# kumand.net
KiCad netlist of a schematic drawn in EAGLE
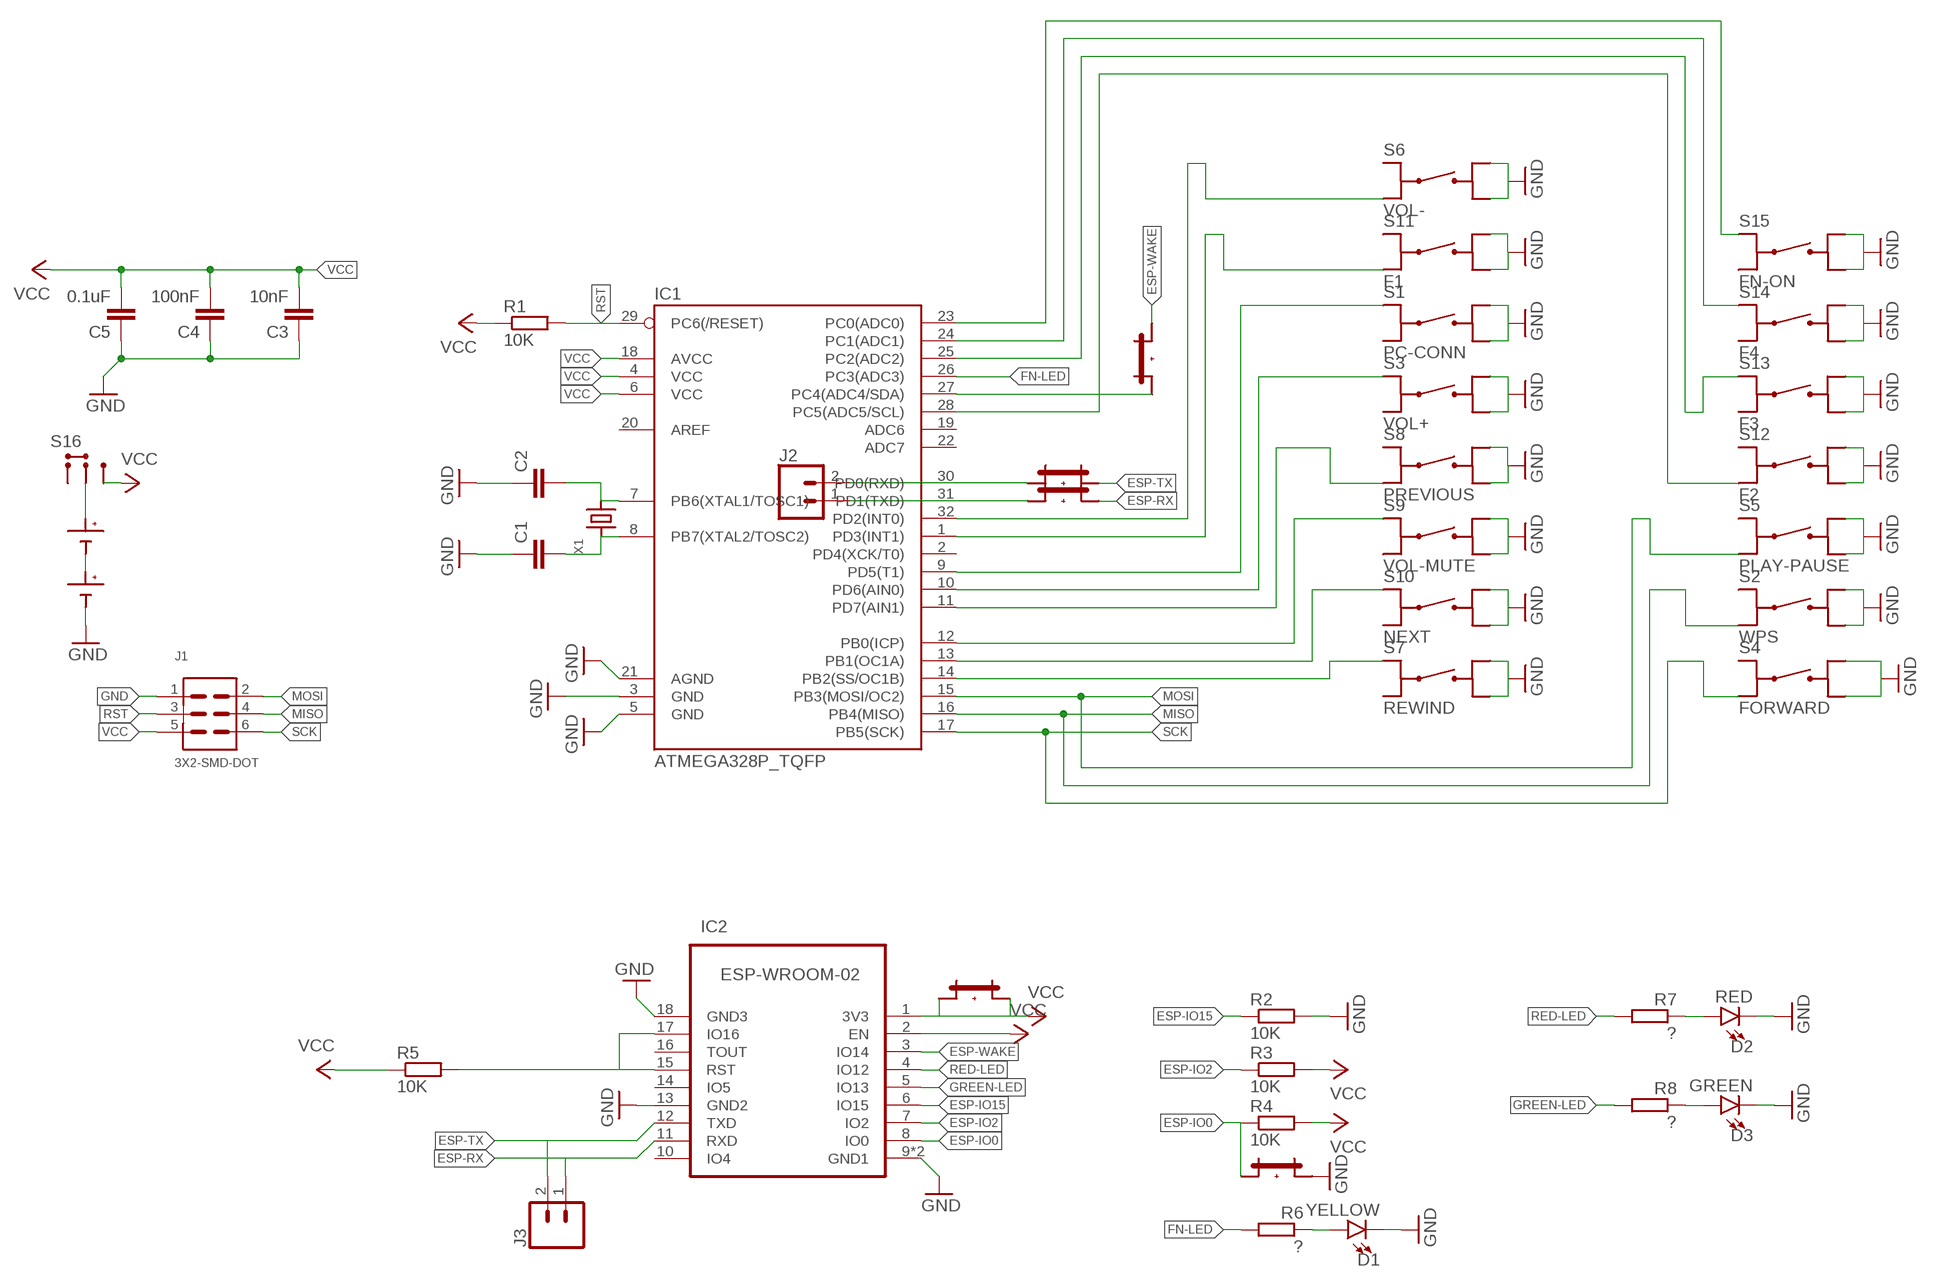
[diagram p0: schematic, sheet 1]

(export (version "E")
  (design (tool "Eeschema 10.0.6"))
  (components
    (comp (ref "C1")
      (value "C-EUC1206")
      (footprint "eagle-import:C1206")
      (libsource (lib "eagle-import") (part "C-EUC1206"))
    )
    (comp (ref "C2")
      (value "C-EUC1206")
      (footprint "eagle-import:C1206")
      (libsource (lib "eagle-import") (part "C-EUC1206"))
    )
    (comp (ref "C3")
      (value "10nF")
      (footprint "eagle-import:C1206")
      (libsource (lib "eagle-import") (part "C-EUC1206"))
    )
    (comp (ref "C4")
      (value "100nF")
      (footprint "eagle-import:C1206")
      (libsource (lib "eagle-import") (part "C-EUC1206"))
    )
    (comp (ref "C5")
      (value "0.1uF")
      (footprint "eagle-import:C1206")
      (libsource (lib "eagle-import") (part "C-EUC1206"))
    )
    (comp (ref "D1")
      (value "YELLOW")
      (footprint "eagle-import:LED-1206")
      (libsource (lib "eagle-import") (part "LED1206"))
    )
    (comp (ref "D2")
      (value "RED")
      (footprint "eagle-import:LED-1206")
      (libsource (lib "eagle-import") (part "LED1206"))
    )
    (comp (ref "D3")
      (value "GREEN")
      (footprint "eagle-import:LED-1206")
      (libsource (lib "eagle-import") (part "LED1206"))
    )
    (comp (ref "IC1")
      (value "ATMEGA328P_TQFP")
      (footprint "eagle-import:TQFP32-08")
      (libsource (lib "eagle-import") (part "ATMEGA328P_TQFP"))
    )
    (comp (ref "IC2")
      (value "ESP-WROOM-02")
      (footprint "eagle-import:FRONT-FACE")
      (libsource (lib "eagle-import") (part "ESP-WROOM-02FRONT-FACE"))
    )
    (comp (ref "J1")
      (value "3X2-SMD-DOT")
      (footprint "eagle-import:3X2-SMD-DOT")
      (libsource (lib "eagle-import") (part "3X2-SMD-DOT"))
    )
    (comp (ref "J2")
      (value "CONN_02")
      (footprint "eagle-import:1X02")
      (libsource (lib "eagle-import") (part "CONN_02"))
    )
    (comp (ref "J3")
      (value "CONN_02")
      (footprint "eagle-import:1X02")
      (libsource (lib "eagle-import") (part "CONN_02"))
    )
    (comp (ref "PRG")
      (value "SOLDER-JUMPER")
      (footprint "eagle-import:SOLDER-JUMPER-PACKAGE")
      (libsource (lib "eagle-import") (part "SOLDER-JUMPER"))
    )
    (comp (ref "R1")
      (value "10K")
      (footprint "eagle-import:R1206")
      (libsource (lib "eagle-import") (part "resistor_348_R-EU_R1206"))
    )
    (comp (ref "R2")
      (value "10K")
      (footprint "eagle-import:R1206")
      (libsource (lib "eagle-import") (part "R-EU_R1206"))
    )
    (comp (ref "R3")
      (value "10K")
      (footprint "eagle-import:R1206")
      (libsource (lib "eagle-import") (part "R-EU_R1206"))
    )
    (comp (ref "R4")
      (value "10K")
      (footprint "eagle-import:R1206")
      (libsource (lib "eagle-import") (part "R-EU_R1206"))
    )
    (comp (ref "R5")
      (value "10K")
      (footprint "eagle-import:R1206")
      (libsource (lib "eagle-import") (part "R-EU_R1206"))
    )
    (comp (ref "R6")
      (value "?")
      (footprint "eagle-import:R1206")
      (libsource (lib "eagle-import") (part "R-EU_R1206"))
    )
    (comp (ref "R7")
      (value "?")
      (footprint "eagle-import:R1206")
      (libsource (lib "eagle-import") (part "R-EU_R1206"))
    )
    (comp (ref "R8")
      (value "?")
      (footprint "eagle-import:R1206")
      (libsource (lib "eagle-import") (part "R-EU_R1206"))
    )
    (comp (ref "RX")
      (value "SOLDER-JUMPER")
      (footprint "eagle-import:SOLDER-JUMPER-PACKAGE")
      (libsource (lib "eagle-import") (part "SOLDER-JUMPER"))
    )
    (comp (ref "S1")
      (value "PC-CONN")
      (footprint "eagle-import:PTS525")
      (libsource (lib "eagle-import") (part "PTS525"))
    )
    (comp (ref "S2")
      (value "WPS")
      (footprint "eagle-import:PTS525")
      (libsource (lib "eagle-import") (part "PTS525"))
    )
    (comp (ref "S3")
      (value "VOL+")
      (footprint "eagle-import:PTS525")
      (libsource (lib "eagle-import") (part "PTS525"))
    )
    (comp (ref "S4")
      (value "FORWARD")
      (footprint "eagle-import:PTS525")
      (libsource (lib "eagle-import") (part "PTS525"))
    )
    (comp (ref "S5")
      (value "PLAY-PAUSE")
      (footprint "eagle-import:PTS525")
      (libsource (lib "eagle-import") (part "PTS525"))
    )
    (comp (ref "S6")
      (value "VOL-")
      (footprint "eagle-import:PTS525")
      (libsource (lib "eagle-import") (part "PTS525"))
    )
    (comp (ref "S7")
      (value "REWIND")
      (footprint "eagle-import:PTS525")
      (libsource (lib "eagle-import") (part "PTS525"))
    )
    (comp (ref "S8")
      (value "PREVIOUS")
      (footprint "eagle-import:PTS525")
      (libsource (lib "eagle-import") (part "PTS525"))
    )
    (comp (ref "S9")
      (value "VOL-MUTE")
      (footprint "eagle-import:PTS525")
      (libsource (lib "eagle-import") (part "PTS525"))
    )
    (comp (ref "S10")
      (value "NEXT")
      (footprint "eagle-import:PTS525")
      (libsource (lib "eagle-import") (part "PTS525"))
    )
    (comp (ref "S11")
      (value "F1")
      (footprint "eagle-import:PTS525")
      (libsource (lib "eagle-import") (part "PTS525"))
    )
    (comp (ref "S12")
      (value "F2")
      (footprint "eagle-import:PTS525")
      (libsource (lib "eagle-import") (part "PTS525"))
    )
    (comp (ref "S13")
      (value "F3")
      (footprint "eagle-import:PTS525")
      (libsource (lib "eagle-import") (part "PTS525"))
    )
    (comp (ref "S14")
      (value "F4")
      (footprint "eagle-import:PTS525")
      (libsource (lib "eagle-import") (part "PTS525"))
    )
    (comp (ref "S15")
      (value "FN-ON")
      (footprint "eagle-import:PTS525")
      (libsource (lib "eagle-import") (part "PTS525"))
    )
    (comp (ref "S16")
      (value "CL-SB-12B-02T")
      (footprint "eagle-import:CL-SB-12B-02T-PACKAGE")
      (libsource (lib "eagle-import") (part "CL-SB-12B-02T"))
    )
    (comp (ref "TX")
      (value "SOLDER-JUMPER")
      (footprint "eagle-import:SOLDER-JUMPER-PACKAGE")
      (libsource (lib "eagle-import") (part "SOLDER-JUMPER"))
    )
    (comp (ref "U$4")
      (value "BK-82-DEVICE")
      (footprint "eagle-import:BK-82-PACKAGE")
      (libsource (lib "eagle-import") (part "BK-82-DEVICE"))
    )
    (comp (ref "U$5")
      (value "BK-82-DEVICE")
      (footprint "eagle-import:BK-82-PACKAGE")
      (libsource (lib "eagle-import") (part "BK-82-DEVICE"))
    )
    (comp (ref "VCC")
      (value "SOLDER-JUMPER")
      (footprint "eagle-import:SOLDER-JUMPER-PACKAGE")
      (libsource (lib "eagle-import") (part "SOLDER-JUMPER"))
    )
    (comp (ref "WAKE")
      (value "SOLDER-JUMPER")
      (footprint "eagle-import:SOLDER-JUMPER-PACKAGE")
      (libsource (lib "eagle-import") (part "SOLDER-JUMPER"))
    )
    (comp (ref "X1")
      (value "NX8045-CRYSTAL")
      (footprint "eagle-import:NX8045")
      (libsource (lib "eagle-import") (part "NX8045-CRYSTAL"))
    )
  )
  (nets
    (net (code "1") (name "ESP-IO0") (class "Default")
      (node (ref "IC2") (pin "8") (pinfunction "IO0_8") (pintype "bidirectional"))
      (node (ref "PRG") (pin "1") (pinfunction "P$1_1") (pintype "bidirectional"))
      (node (ref "R4") (pin "1") (pinfunction "1_1") (pintype "passive"))
    )
    (net (code "2") (name "ESP-IO2") (class "Default")
      (node (ref "IC2") (pin "7") (pinfunction "IO2_7") (pintype "bidirectional"))
      (node (ref "R3") (pin "1") (pinfunction "1_1") (pintype "passive"))
    )
    (net (code "3") (name "ESP-IO15") (class "Default")
      (node (ref "IC2") (pin "6") (pinfunction "IO15_6") (pintype "bidirectional"))
      (node (ref "R2") (pin "1") (pinfunction "1_1") (pintype "passive"))
    )
    (net (code "4") (name "ESP-RX") (class "Default")
      (node (ref "IC2") (pin "11") (pinfunction "RXD_11") (pintype "bidirectional"))
      (node (ref "J3") (pin "1") (pinfunction "1_1") (pintype "passive"))
      (node (ref "RX") (pin "2") (pinfunction "P$2_2") (pintype "bidirectional"))
    )
    (net (code "5") (name "ESP-TX") (class "Default")
      (node (ref "IC2") (pin "12") (pinfunction "TXD_12") (pintype "bidirectional"))
      (node (ref "J3") (pin "2") (pinfunction "2_2") (pintype "passive"))
      (node (ref "TX") (pin "2") (pinfunction "P$2_2") (pintype "bidirectional"))
    )
    (net (code "6") (name "ESP-WAKE") (class "Default")
      (node (ref "IC2") (pin "3") (pinfunction "IO14_3") (pintype "bidirectional"))
      (node (ref "WAKE") (pin "2") (pinfunction "P$2_2") (pintype "bidirectional"))
    )
    (net (code "7") (name "FN-LED") (class "Default")
      (node (ref "IC1") (pin "26") (pinfunction "PC3(ADC3)_26") (pintype "bidirectional"))
      (node (ref "R6") (pin "2") (pinfunction "2_2") (pintype "passive"))
    )
    (net (code "8") (name "GND") (class "Default")
      (node (ref "C1") (pin "1") (pinfunction "1_1") (pintype "passive"))
      (node (ref "C2") (pin "1") (pinfunction "1_1") (pintype "passive"))
      (node (ref "C3") (pin "1") (pinfunction "1_1") (pintype "passive"))
      (node (ref "C4") (pin "1") (pinfunction "1_1") (pintype "passive"))
      (node (ref "C5") (pin "1") (pinfunction "1_1") (pintype "passive"))
      (node (ref "D1") (pin "C") (pinfunction "C_C") (pintype "passive"))
      (node (ref "D2") (pin "C") (pinfunction "C_C") (pintype "passive"))
      (node (ref "D3") (pin "C") (pinfunction "C_C") (pintype "passive"))
      (node (ref "IC1") (pin "21") (pinfunction "AGND_21") (pintype "bidirectional"))
      (node (ref "IC1") (pin "3") (pinfunction "GND_3") (pintype "bidirectional"))
      (node (ref "IC1") (pin "5") (pinfunction "GND_5") (pintype "bidirectional"))
      (node (ref "IC2") (pin "13") (pinfunction "GND2_13") (pintype "power_in"))
      (node (ref "IC2") (pin "18") (pinfunction "GND3_18") (pintype "power_in"))
      (node (ref "IC2") (pin "9") (pinfunction "GND1_9") (pintype "power_in"))
      (node (ref "IC2") (pin "GND") (pinfunction "GND1_GND") (pintype "power_in"))
      (node (ref "J1") (pin "1") (pinfunction "P$1_1") (pintype "bidirectional"))
      (node (ref "PRG") (pin "2") (pinfunction "P$2_2") (pintype "bidirectional"))
      (node (ref "R2") (pin "2") (pinfunction "2_2") (pintype "passive"))
      (node (ref "S1") (pin "3") (pinfunction "P$3_3") (pintype "bidirectional"))
      (node (ref "S1") (pin "4") (pinfunction "P$4_4") (pintype "bidirectional"))
      (node (ref "S10") (pin "3") (pinfunction "P$3_3") (pintype "bidirectional"))
      (node (ref "S10") (pin "4") (pinfunction "P$4_4") (pintype "bidirectional"))
      (node (ref "S11") (pin "3") (pinfunction "P$3_3") (pintype "bidirectional"))
      (node (ref "S11") (pin "4") (pinfunction "P$4_4") (pintype "bidirectional"))
      (node (ref "S12") (pin "3") (pinfunction "P$3_3") (pintype "bidirectional"))
      (node (ref "S12") (pin "4") (pinfunction "P$4_4") (pintype "bidirectional"))
      (node (ref "S13") (pin "3") (pinfunction "P$3_3") (pintype "bidirectional"))
      (node (ref "S13") (pin "4") (pinfunction "P$4_4") (pintype "bidirectional"))
      (node (ref "S14") (pin "3") (pinfunction "P$3_3") (pintype "bidirectional"))
      (node (ref "S14") (pin "4") (pinfunction "P$4_4") (pintype "bidirectional"))
      (node (ref "S15") (pin "3") (pinfunction "P$3_3") (pintype "bidirectional"))
      (node (ref "S15") (pin "4") (pinfunction "P$4_4") (pintype "bidirectional"))
      (node (ref "S2") (pin "3") (pinfunction "P$3_3") (pintype "bidirectional"))
      (node (ref "S2") (pin "4") (pinfunction "P$4_4") (pintype "bidirectional"))
      (node (ref "S3") (pin "3") (pinfunction "P$3_3") (pintype "bidirectional"))
      (node (ref "S3") (pin "4") (pinfunction "P$4_4") (pintype "bidirectional"))
      (node (ref "S4") (pin "3") (pinfunction "P$3_3") (pintype "bidirectional"))
      (node (ref "S4") (pin "4") (pinfunction "P$4_4") (pintype "bidirectional"))
      (node (ref "S5") (pin "3") (pinfunction "P$3_3") (pintype "bidirectional"))
      (node (ref "S5") (pin "4") (pinfunction "P$4_4") (pintype "bidirectional"))
      (node (ref "S6") (pin "3") (pinfunction "P$3_3") (pintype "bidirectional"))
      (node (ref "S6") (pin "4") (pinfunction "P$4_4") (pintype "bidirectional"))
      (node (ref "S7") (pin "3") (pinfunction "P$3_3") (pintype "bidirectional"))
      (node (ref "S7") (pin "4") (pinfunction "P$4_4") (pintype "bidirectional"))
      (node (ref "S8") (pin "3") (pinfunction "P$3_3") (pintype "bidirectional"))
      (node (ref "S8") (pin "4") (pinfunction "P$4_4") (pintype "bidirectional"))
      (node (ref "S9") (pin "3") (pinfunction "P$3_3") (pintype "bidirectional"))
      (node (ref "S9") (pin "4") (pinfunction "P$4_4") (pintype "bidirectional"))
      (node (ref "U$5") (pin "P$2") (pinfunction "P$2_P$2") (pintype "bidirectional"))
      (node (ref "U$5") (pin "P$4") (pinfunction "P$2_P$4") (pintype "bidirectional"))
    )
    (net (code "9") (name "GREEN-LED") (class "Default")
      (node (ref "IC2") (pin "5") (pinfunction "IO13_5") (pintype "bidirectional"))
      (node (ref "R8") (pin "2") (pinfunction "2_2") (pintype "passive"))
    )
    (net (code "10") (name "MISO") (class "Default")
      (node (ref "IC1") (pin "16") (pinfunction "PB4(MISO)_16") (pintype "bidirectional"))
      (node (ref "J1") (pin "4") (pinfunction "P$4_4") (pintype "bidirectional"))
      (node (ref "S2") (pin "2") (pinfunction "P$2_2") (pintype "bidirectional"))
    )
    (net (code "11") (name "MOSI") (class "Default")
      (node (ref "IC1") (pin "15") (pinfunction "PB3(MOSI/OC2)_15") (pintype "bidirectional"))
      (node (ref "J1") (pin "2") (pinfunction "P$2_2") (pintype "bidirectional"))
      (node (ref "S5") (pin "2") (pinfunction "P$2_2") (pintype "bidirectional"))
    )
    (net (code "12") (name "Net-(D1-PadA)") (class "Default")
      (node (ref "D1") (pin "A") (pinfunction "A_A") (pintype "passive"))
      (node (ref "R6") (pin "1") (pinfunction "1_1") (pintype "passive"))
    )
    (net (code "13") (name "Net-(D2-PadA)") (class "Default")
      (node (ref "D2") (pin "A") (pinfunction "A_A") (pintype "passive"))
      (node (ref "R7") (pin "1") (pinfunction "1_1") (pintype "passive"))
    )
    (net (code "14") (name "Net-(D3-PadA)") (class "Default")
      (node (ref "D3") (pin "A") (pinfunction "A_A") (pintype "passive"))
      (node (ref "R8") (pin "1") (pinfunction "1_1") (pintype "passive"))
    )
    (net (code "15") (name "Net-(IC1-PB0(ICP))") (class "Default")
      (node (ref "IC1") (pin "12") (pinfunction "PB0(ICP)_12") (pintype "bidirectional"))
      (node (ref "S9") (pin "1") (pinfunction "P$1_1") (pintype "bidirectional"))
    )
    (net (code "16") (name "Net-(IC1-PB1(OC1A))") (class "Default")
      (node (ref "IC1") (pin "13") (pinfunction "PB1(OC1A)_13") (pintype "bidirectional"))
      (node (ref "S10") (pin "1") (pinfunction "P$1_1") (pintype "bidirectional"))
    )
    (net (code "17") (name "Net-(IC1-PB2(SS{slash}OC1B))") (class "Default")
      (node (ref "IC1") (pin "14") (pinfunction "PB2(SS/OC1B)_14") (pintype "bidirectional"))
      (node (ref "S7") (pin "1") (pinfunction "P$1_1") (pintype "bidirectional"))
    )
    (net (code "18") (name "Net-(IC1-PB6(XTAL1{slash}TOSC1))") (class "Default")
      (node (ref "C2") (pin "2") (pinfunction "2_2") (pintype "passive"))
      (node (ref "IC1") (pin "7") (pinfunction "PB6(XTAL1/TOSC1)_7") (pintype "bidirectional"))
      (node (ref "X1") (pin "P$2") (pinfunction "P$2_P$2") (pintype "passive"))
    )
    (net (code "19") (name "Net-(IC1-PB7(XTAL2{slash}TOSC2))") (class "Default")
      (node (ref "C1") (pin "2") (pinfunction "2_2") (pintype "passive"))
      (node (ref "IC1") (pin "8") (pinfunction "PB7(XTAL2/TOSC2)_8") (pintype "bidirectional"))
      (node (ref "X1") (pin "P$1") (pinfunction "P$1_P$1") (pintype "passive"))
    )
    (net (code "20") (name "Net-(IC1-PC0(ADC0))") (class "Default")
      (node (ref "IC1") (pin "23") (pinfunction "PC0(ADC0)_23") (pintype "bidirectional"))
      (node (ref "S15") (pin "1") (pinfunction "P$1_1") (pintype "bidirectional"))
    )
    (net (code "21") (name "Net-(IC1-PC1(ADC1))") (class "Default")
      (node (ref "IC1") (pin "24") (pinfunction "PC1(ADC1)_24") (pintype "bidirectional"))
      (node (ref "S14") (pin "1") (pinfunction "P$1_1") (pintype "bidirectional"))
    )
    (net (code "22") (name "Net-(IC1-PC2(ADC2))") (class "Default")
      (node (ref "IC1") (pin "25") (pinfunction "PC2(ADC2)_25") (pintype "bidirectional"))
      (node (ref "S13") (pin "1") (pinfunction "P$1_1") (pintype "bidirectional"))
    )
    (net (code "23") (name "Net-(IC1-PC4(ADC4{slash}SDA))") (class "Default")
      (node (ref "IC1") (pin "27") (pinfunction "PC4(ADC4/SDA)_27") (pintype "bidirectional"))
      (node (ref "WAKE") (pin "1") (pinfunction "P$1_1") (pintype "bidirectional"))
    )
    (net (code "24") (name "Net-(IC1-PC5(ADC5{slash}SCL))") (class "Default")
      (node (ref "IC1") (pin "28") (pinfunction "PC5(ADC5/SCL)_28") (pintype "bidirectional"))
      (node (ref "S12") (pin "2") (pinfunction "P$2_2") (pintype "bidirectional"))
    )
    (net (code "25") (name "Net-(IC1-PD0(RXD))") (class "Default")
      (node (ref "IC1") (pin "30") (pinfunction "PD0(RXD)_30") (pintype "bidirectional"))
      (node (ref "J2") (pin "2") (pinfunction "2_2") (pintype "passive"))
      (node (ref "TX") (pin "1") (pinfunction "P$1_1") (pintype "bidirectional"))
    )
    (net (code "26") (name "Net-(IC1-PD1(TXD))") (class "Default")
      (node (ref "IC1") (pin "31") (pinfunction "PD1(TXD)_31") (pintype "bidirectional"))
      (node (ref "J2") (pin "1") (pinfunction "1_1") (pintype "passive"))
      (node (ref "RX") (pin "1") (pinfunction "P$1_1") (pintype "bidirectional"))
    )
    (net (code "27") (name "Net-(IC1-PD2(INT0))") (class "Default")
      (node (ref "IC1") (pin "32") (pinfunction "PD2(INT0)_32") (pintype "bidirectional"))
      (node (ref "S6") (pin "2") (pinfunction "P$2_2") (pintype "bidirectional"))
    )
    (net (code "28") (name "Net-(IC1-PD3(INT1))") (class "Default")
      (node (ref "IC1") (pin "1") (pinfunction "PD3(INT1)_1") (pintype "bidirectional"))
      (node (ref "S11") (pin "2") (pinfunction "P$2_2") (pintype "bidirectional"))
    )
    (net (code "29") (name "Net-(IC1-PD5(T1))") (class "Default")
      (node (ref "IC1") (pin "9") (pinfunction "PD5(T1)_9") (pintype "bidirectional"))
      (node (ref "S1") (pin "1") (pinfunction "P$1_1") (pintype "bidirectional"))
    )
    (net (code "30") (name "Net-(IC1-PD6(AIN0))") (class "Default")
      (node (ref "IC1") (pin "10") (pinfunction "PD6(AIN0)_10") (pintype "bidirectional"))
      (node (ref "S3") (pin "1") (pinfunction "P$1_1") (pintype "bidirectional"))
    )
    (net (code "31") (name "Net-(IC1-PD7(AIN1))") (class "Default")
      (node (ref "IC1") (pin "11") (pinfunction "PD7(AIN1)_11") (pintype "bidirectional"))
      (node (ref "S8") (pin "2") (pinfunction "P$2_2") (pintype "bidirectional"))
    )
    (net (code "32") (name "Net-(IC2-IO16)") (class "Default")
      (node (ref "IC2") (pin "15") (pinfunction "RST_15") (pintype "bidirectional"))
      (node (ref "IC2") (pin "17") (pinfunction "IO16_17") (pintype "bidirectional"))
      (node (ref "R5") (pin "2") (pinfunction "2_2") (pintype "passive"))
    )
    (net (code "33") (name "Net-(S16-PadP$2)") (class "Default")
      (node (ref "S16") (pin "P$2") (pinfunction "P$2_P$2") (pintype "bidirectional"))
      (node (ref "U$4") (pin "P$1") (pinfunction "P$1_P$1") (pintype "bidirectional"))
      (node (ref "U$4") (pin "P$3") (pinfunction "P$1_P$3") (pintype "bidirectional"))
    )
    (net (code "34") (name "Net-(U$4-P$2-PadP$4)") (class "Default")
      (node (ref "U$4") (pin "P$2") (pinfunction "P$2_P$2") (pintype "bidirectional"))
      (node (ref "U$4") (pin "P$4") (pinfunction "P$2_P$4") (pintype "bidirectional"))
      (node (ref "U$5") (pin "P$1") (pinfunction "P$1_P$1") (pintype "bidirectional"))
      (node (ref "U$5") (pin "P$3") (pinfunction "P$1_P$3") (pintype "bidirectional"))
    )
    (net (code "35") (name "RED-LED") (class "Default")
      (node (ref "IC2") (pin "4") (pinfunction "IO12_4") (pintype "bidirectional"))
      (node (ref "R7") (pin "2") (pinfunction "2_2") (pintype "passive"))
    )
    (net (code "36") (name "RST") (class "Default")
      (node (ref "IC1") (pin "29") (pinfunction "PC6(/RESET)_29") (pintype "bidirectional"))
      (node (ref "J1") (pin "3") (pinfunction "P$3_3") (pintype "bidirectional"))
      (node (ref "R1") (pin "2") (pinfunction "2_2") (pintype "passive"))
    )
    (net (code "37") (name "SCK") (class "Default")
      (node (ref "IC1") (pin "17") (pinfunction "PB5(SCK)_17") (pintype "bidirectional"))
      (node (ref "J1") (pin "6") (pinfunction "P$6_6") (pintype "bidirectional"))
      (node (ref "S4") (pin "2") (pinfunction "P$2_2") (pintype "bidirectional"))
    )
    (net (code "38") (name "VCC") (class "Default")
      (node (ref "C3") (pin "2") (pinfunction "2_2") (pintype "passive"))
      (node (ref "C4") (pin "2") (pinfunction "2_2") (pintype "passive"))
      (node (ref "C5") (pin "2") (pinfunction "2_2") (pintype "passive"))
      (node (ref "IC1") (pin "18") (pinfunction "AVCC_18") (pintype "bidirectional"))
      (node (ref "IC1") (pin "4") (pinfunction "VCC_4") (pintype "bidirectional"))
      (node (ref "IC1") (pin "6") (pinfunction "VCC_6") (pintype "bidirectional"))
      (node (ref "IC2") (pin "1") (pinfunction "3V3_1") (pintype "power_in"))
      (node (ref "IC2") (pin "2") (pinfunction "EN_2") (pintype "bidirectional"))
      (node (ref "J1") (pin "5") (pinfunction "P$5_5") (pintype "bidirectional"))
      (node (ref "R1") (pin "1") (pinfunction "1_1") (pintype "passive"))
      (node (ref "R3") (pin "2") (pinfunction "2_2") (pintype "passive"))
      (node (ref "R4") (pin "2") (pinfunction "2_2") (pintype "passive"))
      (node (ref "R5") (pin "1") (pinfunction "1_1") (pintype "passive"))
      (node (ref "S16") (pin "P$3") (pinfunction "P$3_P$3") (pintype "bidirectional"))
      (node (ref "VCC") (pin "1") (pinfunction "P$1_1") (pintype "bidirectional"))
      (node (ref "VCC") (pin "2") (pinfunction "P$2_2") (pintype "bidirectional"))
    )
    (net (code "39") (name "unconnected-(IC1-ADC6-Pad19)") (class "Default")
      (node (ref "IC1") (pin "19") (pinfunction "ADC6_19") (pintype "bidirectional"))
    )
    (net (code "40") (name "unconnected-(IC1-ADC7-Pad22)") (class "Default")
      (node (ref "IC1") (pin "22") (pinfunction "ADC7_22") (pintype "bidirectional"))
    )
    (net (code "41") (name "unconnected-(IC1-AREF-Pad20)") (class "Default")
      (node (ref "IC1") (pin "20") (pinfunction "AREF_20") (pintype "bidirectional"))
    )
    (net (code "42") (name "unconnected-(IC1-PD4(XCK{slash}T0)-Pad2)") (class "Default")
      (node (ref "IC1") (pin "2") (pinfunction "PD4(XCK/T0)_2") (pintype "bidirectional"))
    )
    (net (code "43") (name "unconnected-(IC2-IO4-Pad10)") (class "Default")
      (node (ref "IC2") (pin "10") (pinfunction "IO4_10") (pintype "bidirectional"))
    )
    (net (code "44") (name "unconnected-(IC2-IO5-Pad14)") (class "Default")
      (node (ref "IC2") (pin "14") (pinfunction "IO5_14") (pintype "open_collector"))
    )
    (net (code "45") (name "unconnected-(IC2-TOUT-Pad16)") (class "Default")
      (node (ref "IC2") (pin "16") (pinfunction "TOUT_16") (pintype "bidirectional"))
    )
    (net (code "46") (name "unconnected-(S1-P$2-Pad2)") (class "Default")
      (node (ref "S1") (pin "2") (pinfunction "P$2_2") (pintype "bidirectional"))
    )
    (net (code "47") (name "unconnected-(S2-P$1-Pad1)") (class "Default")
      (node (ref "S2") (pin "1") (pinfunction "P$1_1") (pintype "bidirectional"))
    )
    (net (code "48") (name "unconnected-(S3-P$2-Pad2)") (class "Default")
      (node (ref "S3") (pin "2") (pinfunction "P$2_2") (pintype "bidirectional"))
    )
    (net (code "49") (name "unconnected-(S4-P$1-Pad1)") (class "Default")
      (node (ref "S4") (pin "1") (pinfunction "P$1_1") (pintype "bidirectional"))
    )
    (net (code "50") (name "unconnected-(S5-P$1-Pad1)") (class "Default")
      (node (ref "S5") (pin "1") (pinfunction "P$1_1") (pintype "bidirectional"))
    )
    (net (code "51") (name "unconnected-(S6-P$1-Pad1)") (class "Default")
      (node (ref "S6") (pin "1") (pinfunction "P$1_1") (pintype "bidirectional"))
    )
    (net (code "52") (name "unconnected-(S7-P$2-Pad2)") (class "Default")
      (node (ref "S7") (pin "2") (pinfunction "P$2_2") (pintype "bidirectional"))
    )
    (net (code "53") (name "unconnected-(S8-P$1-Pad1)") (class "Default")
      (node (ref "S8") (pin "1") (pinfunction "P$1_1") (pintype "bidirectional"))
    )
    (net (code "54") (name "unconnected-(S9-P$2-Pad2)") (class "Default")
      (node (ref "S9") (pin "2") (pinfunction "P$2_2") (pintype "bidirectional"))
    )
    (net (code "55") (name "unconnected-(S10-P$2-Pad2)") (class "Default")
      (node (ref "S10") (pin "2") (pinfunction "P$2_2") (pintype "bidirectional"))
    )
    (net (code "56") (name "unconnected-(S11-P$1-Pad1)") (class "Default")
      (node (ref "S11") (pin "1") (pinfunction "P$1_1") (pintype "bidirectional"))
    )
    (net (code "57") (name "unconnected-(S12-P$1-Pad1)") (class "Default")
      (node (ref "S12") (pin "1") (pinfunction "P$1_1") (pintype "bidirectional"))
    )
    (net (code "58") (name "unconnected-(S13-P$2-Pad2)") (class "Default")
      (node (ref "S13") (pin "2") (pinfunction "P$2_2") (pintype "bidirectional"))
    )
    (net (code "59") (name "unconnected-(S14-P$2-Pad2)") (class "Default")
      (node (ref "S14") (pin "2") (pinfunction "P$2_2") (pintype "bidirectional"))
    )
    (net (code "60") (name "unconnected-(S15-P$2-Pad2)") (class "Default")
      (node (ref "S15") (pin "2") (pinfunction "P$2_2") (pintype "bidirectional"))
    )
    (net (code "61") (name "unconnected-(S16-PadP$1)") (class "Default")
      (node (ref "S16") (pin "P$1") (pinfunction "P$1_P$1") (pintype "bidirectional"))
    )
  )
)
